# 3_Power_schdoc.net
KiCad netlist of a schematic drawn in Altium Designer
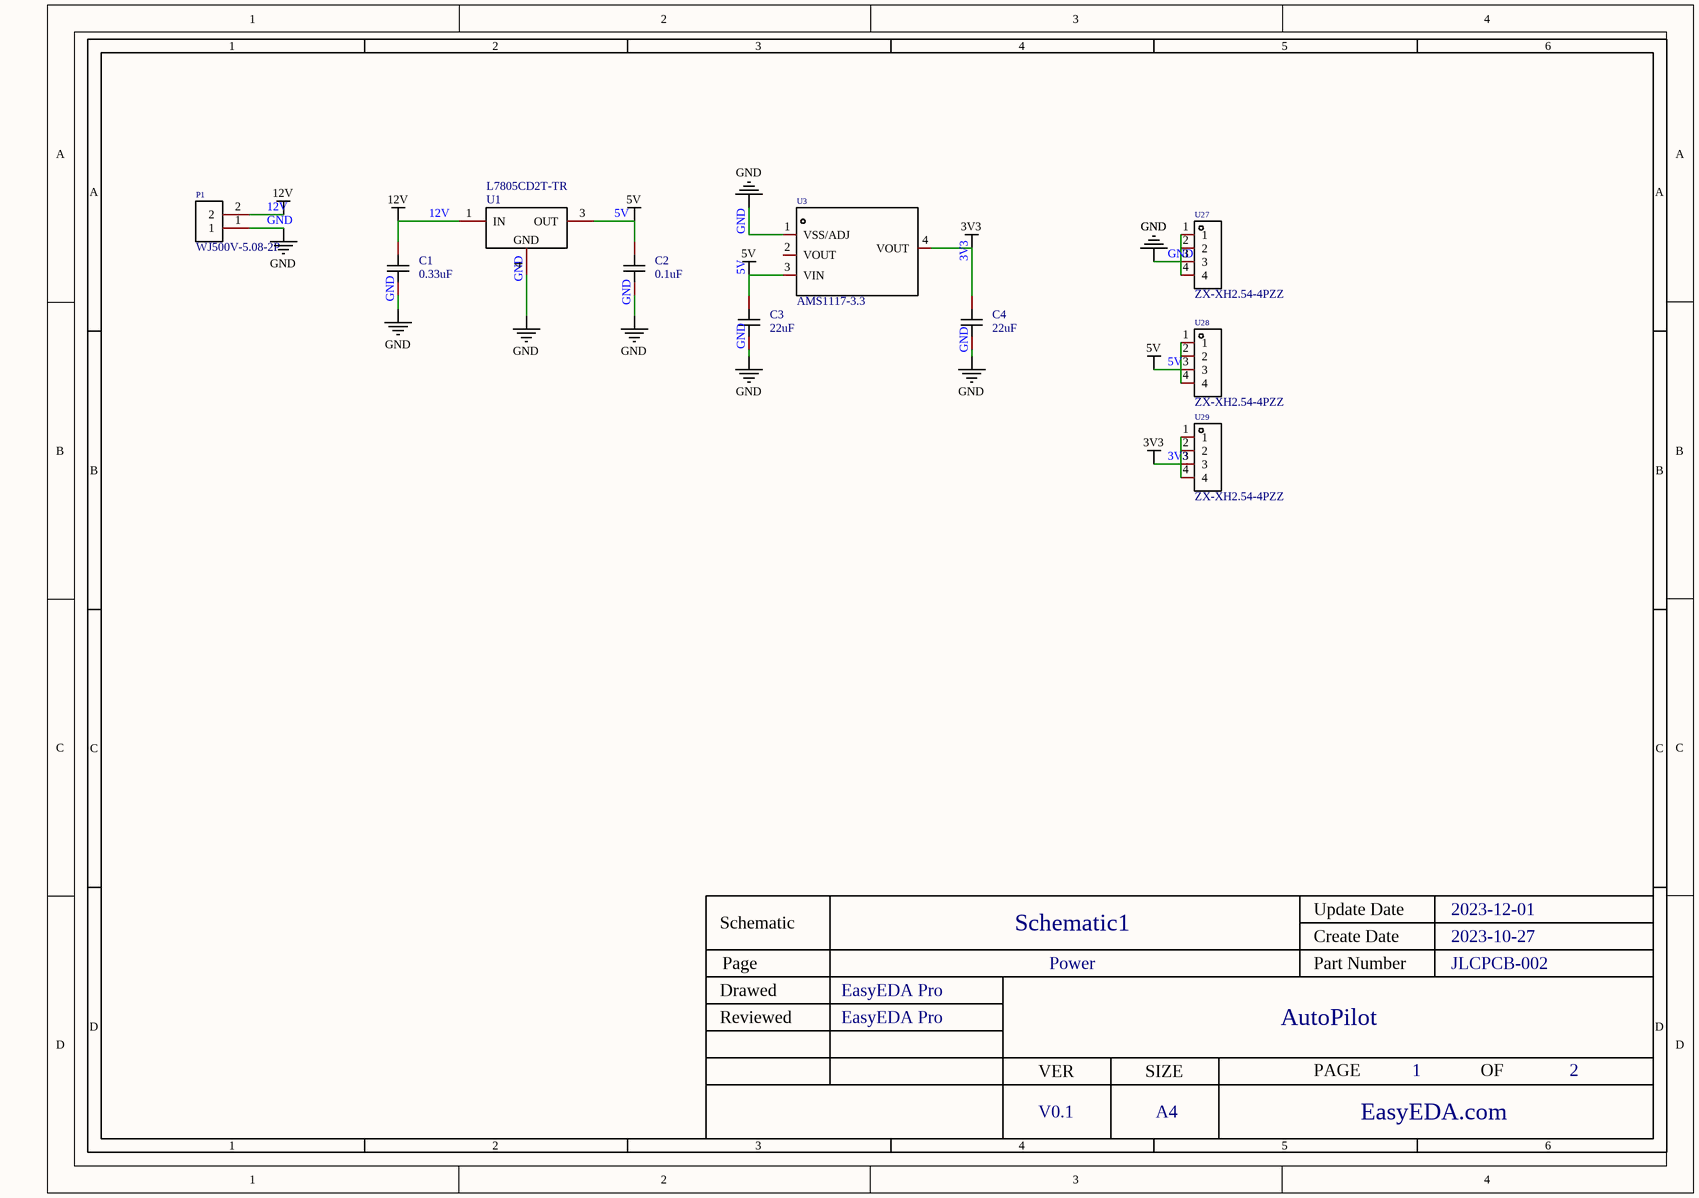
[diagram p0: 3_Power.schdoc.schdoc]

(export (version "E")
  (design (tool "Eeschema 10.0.6"))
  (components
    (comp (ref "C1")
      (value "0.33uF")
      (fields (field (name "NAME") "0.33uF"))
      (libsource (lib "altium-import") (part "root_1_CAP_0603_"))
    )
    (comp (ref "C2")
      (value "0.1uF")
      (fields (field (name "NAME") "0.1uF"))
      (libsource (lib "altium-import") (part "root_1_CAP_0603_"))
    )
    (comp (ref "C3")
      (value "22uF")
      (fields (field (name "NAME") "22uF"))
      (libsource (lib "altium-import") (part "root_1_CAP_0603_"))
    )
    (comp (ref "C4")
      (value "22uF")
      (fields (field (name "NAME") "22uF"))
      (libsource (lib "altium-import") (part "root_1_CAP_0603_"))
    )
    (comp (ref "P1")
      (value "WJ500V-5.08-2P")
      (fields (field (name "NAME") "WJ500V-5.08-2P") (field (name "MANUFACTURER") "KANGNEX(康奈克斯电气)"))
      (libsource (lib "altium-import") (part "root_1_WJ500V-5.08-2P_"))
    )
    (comp (ref "U1")
      (value "L7805CD2T-TR")
      (fields (field (name "NAME") "L7805CD2T-TR") (field (name "MANUFACTURER") "ST(意法半导体)"))
      (libsource (lib "altium-import") (part "root_0_L7805CD2T-TR_"))
    )
    (comp (ref "U3")
      (value "AMS1117-3.3")
      (fields (field (name "NAME") "AMS1117-3.3") (field (name "MANUFACTURER") "HX(恒佳兴)"))
      (libsource (lib "altium-import") (part "root_3_AMS1117-3.3_C5181460_"))
    )
    (comp (ref "U27")
      (value "ZX-XH2.54-4PZZ")
      (fields (field (name "NAME") "ZX-XH2.54-4PZZ") (field (name "MANUFACTURER") "Megastar(兆星)"))
      (libsource (lib "altium-import") (part "root_0_ZX-XH2.54-4PZZ_"))
    )
    (comp (ref "U28")
      (value "ZX-XH2.54-4PZZ")
      (fields (field (name "NAME") "ZX-XH2.54-4PZZ") (field (name "MANUFACTURER") "Megastar(兆星)"))
      (libsource (lib "altium-import") (part "root_0_ZX-XH2.54-4PZZ_"))
    )
    (comp (ref "U29")
      (value "ZX-XH2.54-4PZZ")
      (fields (field (name "NAME") "ZX-XH2.54-4PZZ") (field (name "MANUFACTURER") "Megastar(兆星)"))
      (libsource (lib "altium-import") (part "root_0_ZX-XH2.54-4PZZ_"))
    )
  )
  (nets
    (net (code "1") (name "3V3") (class "Default")
      (node (ref "C4") (pin "1") (pinfunction "1_1") (pintype "passive"))
      (node (ref "U29") (pin "1") (pinfunction "1_1") (pintype "passive"))
      (node (ref "U29") (pin "2") (pinfunction "2_2") (pintype "passive"))
      (node (ref "U29") (pin "3") (pinfunction "3_3") (pintype "passive"))
      (node (ref "U29") (pin "4") (pinfunction "4_4") (pintype "passive"))
      (node (ref "U3") (pin "4") (pinfunction "VOUT_4") (pintype "passive"))
    )
    (net (code "2") (name "5V") (class "Default")
      (node (ref "C2") (pin "1") (pinfunction "1_1") (pintype "passive"))
      (node (ref "C3") (pin "1") (pinfunction "1_1") (pintype "passive"))
      (node (ref "U1") (pin "3") (pinfunction "OUT_3") (pintype "passive"))
      (node (ref "U28") (pin "1") (pinfunction "1_1") (pintype "passive"))
      (node (ref "U28") (pin "2") (pinfunction "2_2") (pintype "passive"))
      (node (ref "U28") (pin "3") (pinfunction "3_3") (pintype "passive"))
      (node (ref "U28") (pin "4") (pinfunction "4_4") (pintype "passive"))
      (node (ref "U3") (pin "3") (pinfunction "VIN_3") (pintype "passive"))
    )
    (net (code "3") (name "12V") (class "Default")
      (node (ref "C1") (pin "1") (pinfunction "1_1") (pintype "passive"))
      (node (ref "P1") (pin "2") (pinfunction "2_2") (pintype "passive"))
      (node (ref "U1") (pin "1") (pinfunction "IN_1") (pintype "passive"))
    )
    (net (code "4") (name "GND") (class "Default")
      (node (ref "C1") (pin "2") (pinfunction "2_2") (pintype "passive"))
      (node (ref "C2") (pin "2") (pinfunction "2_2") (pintype "passive"))
      (node (ref "C3") (pin "2") (pinfunction "2_2") (pintype "passive"))
      (node (ref "C4") (pin "2") (pinfunction "2_2") (pintype "passive"))
      (node (ref "P1") (pin "1") (pinfunction "1_1") (pintype "passive"))
      (node (ref "U1") (pin "4") (pinfunction "GND_4") (pintype "passive"))
      (node (ref "U27") (pin "1") (pinfunction "1_1") (pintype "passive"))
      (node (ref "U27") (pin "2") (pinfunction "2_2") (pintype "passive"))
      (node (ref "U27") (pin "3") (pinfunction "3_3") (pintype "passive"))
      (node (ref "U27") (pin "4") (pinfunction "4_4") (pintype "passive"))
      (node (ref "U3") (pin "1") (pinfunction "VSS/ADJ_1") (pintype "passive"))
    )
    (net (code "5") (name "unconnected-(U3-VOUT-Pad2)") (class "Default")
      (node (ref "U3") (pin "2") (pinfunction "VOUT_2") (pintype "passive"))
    )
  )
)
